# MPPT.net
KiCad netlist of a schematic drawn in Altium Designer
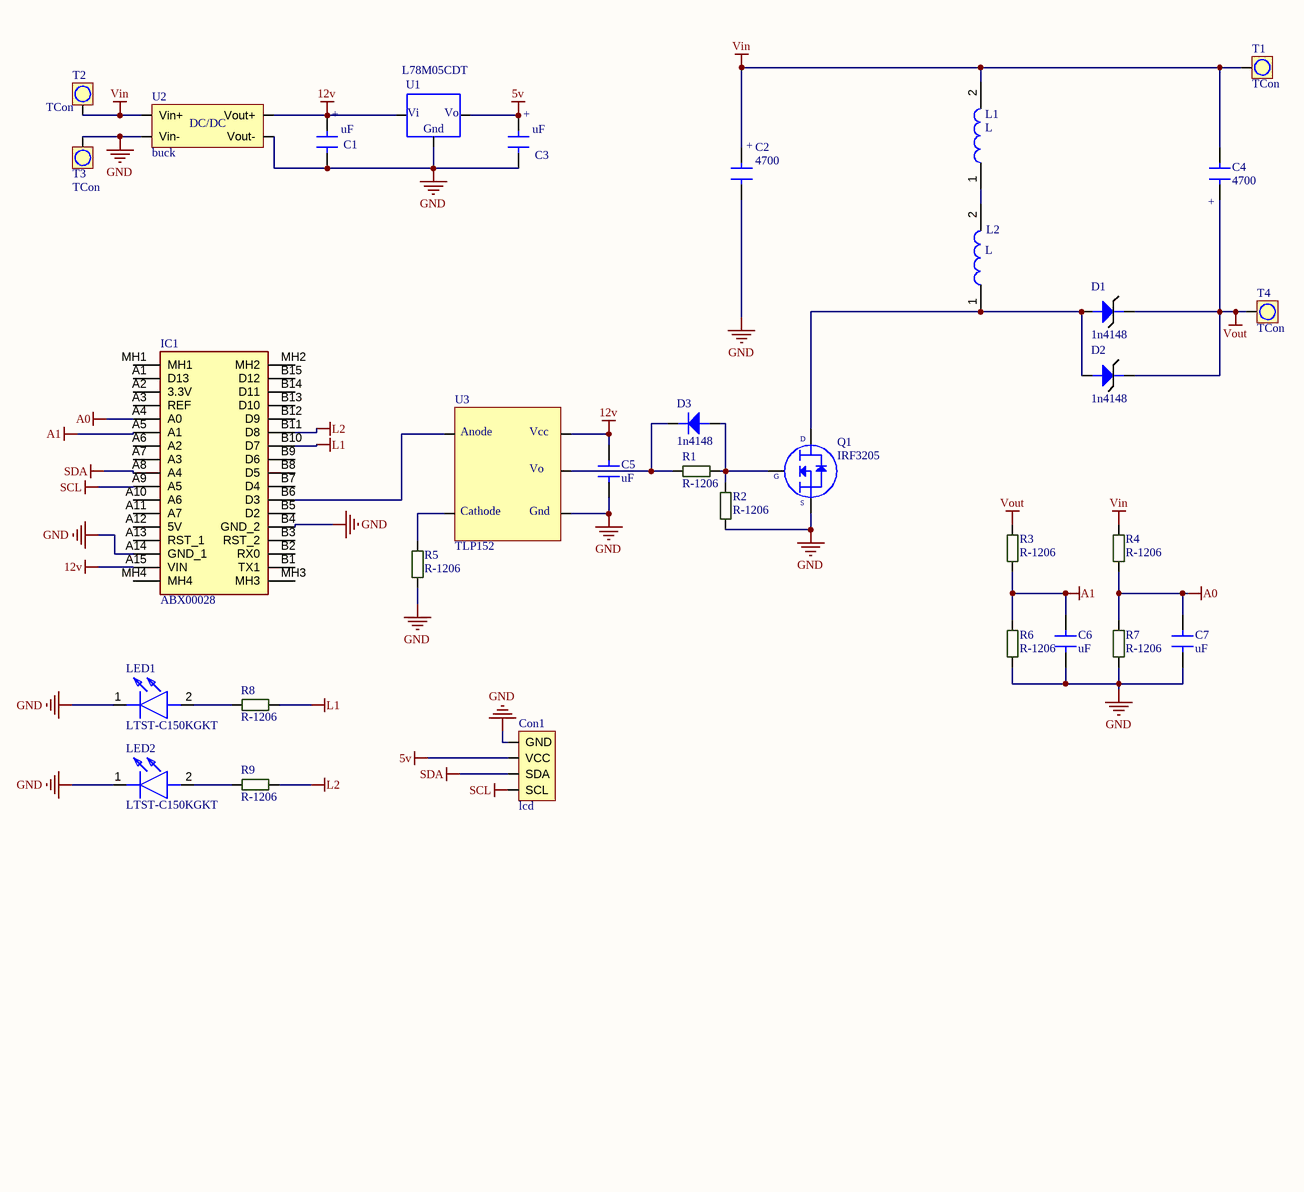
[diagram p0: MPPT.SchDoc]

(export (version "E")
  (design (tool "Eeschema 10.0.6"))
  (components
    (comp (ref "C1") (value "uF") (footprint "CapSmdElc") (libsource (lib "MPPT") (part "C-10uf")))
    (comp (ref "C2") (value "4700") (footprint "Koshin 63v 4700 cap") (libsource (lib "MPPT") (part "4700")))
    (comp (ref "C3") (value "uF") (footprint "CapSmdElc") (libsource (lib "MPPT") (part "C-10uf")))
    (comp (ref "C4") (value "4700") (footprint "Koshin 63v 4700 cap") (libsource (lib "MPPT") (part "4700")))
    (comp (ref "C5") (value "uF") (footprint "C-1206W") (libsource (lib "MPPT") (part "C-1206")))
    (comp (ref "C6") (value "uF") (footprint "C-1206W") (libsource (lib "MPPT") (part "C-1206")))
    (comp (ref "C7") (value "uF") (footprint "C-1206W") (libsource (lib "MPPT") (part "C-1206")))
    (comp (ref "Con1") (value "lcd") (footprint "lcd") (libsource (lib "MPPT") (part "lcd")))
    (comp (ref "D1")
      (value "1n4148")
      (footprint "TO254P483X1016X1994-3P")
      (description "Diode Small Signal Switching 100V 0.15A 2-Pin SOD-123 T/R")
      (fields
        (field (name "MANUFACTURER") "Vishay")
        (field (name "MANUFACTURER PART NUMBER") "1N4148W-E3-18")
      )
      (libsource (lib "MPPT") (part "schotky"))
    )
    (comp (ref "D2")
      (value "1n4148")
      (footprint "TO254P483X1016X1994-3P")
      (description "Diode Small Signal Switching 100V 0.15A 2-Pin SOD-123 T/R")
      (fields
        (field (name "MANUFACTURER") "Vishay")
        (field (name "MANUFACTURER PART NUMBER") "1N4148W-E3-18")
      )
      (libsource (lib "MPPT") (part "schotky"))
    )
    (comp (ref "D3")
      (value "1n4148")
      (footprint "SOD123")
      (description "Diode Small Signal Switching 100V 0.15A 2-Pin SOD-123 T/R")
      (fields
        (field (name "MANUFACTURER") "Vishay")
        (field (name "MANUFACTURER PART NUMBER") "1N4148W-E3-18")
      )
      (libsource (lib "MPPT") (part "1N5819w"))
    )
    (comp (ref "IC1")
      (value "ABX00028")
      (footprint "ABX00028")
      (description "Integrated Circuit")
      (fields (field (name "MOUSER PART NUMBER") "782-ABX00028") (field (name "RS PART NUMBER") "1927586"))
      (libsource (lib "MPPT") (part "ABX00028"))
    )
    (comp (ref "L1")
      (value "L")
      (footprint "L")
      (description "Inductor")
      (fields
        (field (name "MANUFACTURER_PART_NUMBER") "ATFC-0201-10N-G-T")
        (field (name "MOUSER PART NUMBER") "815-ATFC-0201-10NG")
      )
      (libsource (lib "MPPT") (part "L"))
    )
    (comp (ref "L2")
      (value "L")
      (footprint "L")
      (description "Inductor")
      (fields
        (field (name "MANUFACTURER_PART_NUMBER") "ATFC-0201-10N-G-T")
        (field (name "MOUSER PART NUMBER") "815-ATFC-0201-10NG")
      )
      (libsource (lib "MPPT") (part "L"))
    )
    (comp (ref "LED1")
      (value "LTST-C150KGKT")
      (footprint "L-1206")
      (description "LED")
      (fields
        (field (name "MOUSER PART NUMBER") "859-LTST-C150KGKT")
        (field (name "RS PART NUMBER") "6920871")
      )
      (libsource (lib "MPPT") (part "LTST-C150KGKT"))
    )
    (comp (ref "LED2")
      (value "LTST-C150KGKT")
      (footprint "L-1206")
      (description "LED")
      (fields
        (field (name "MOUSER PART NUMBER") "859-LTST-C150KGKT")
        (field (name "RS PART NUMBER") "6920871")
      )
      (libsource (lib "MPPT") (part "LTST-C150KGKT"))
    )
    (comp (ref "Q1")
      (value "IRF3205")
      (footprint "DPAK_TO263")
      (description "MOSFET N-CH 55V 110A D2PAK")
      (fields
        (field (name "MANUFACTURER") "Infineon")
        (field (name "MANUFACTURER PART NUMBER") "IRF3205STRLPBF")
      )
      (libsource (lib "MPPT") (part "IRF3205STRLPBF"))
    )
    (comp (ref "R1")
      (value "R-1206")
      (footprint "R-1206W")
      (description "Res1206")
      (libsource (lib "MPPT") (part "R-1206"))
    )
    (comp (ref "R2")
      (value "R-1206")
      (footprint "R-1206W")
      (description "Res1206")
      (libsource (lib "MPPT") (part "R-1206"))
    )
    (comp (ref "R3")
      (value "R-1206")
      (footprint "R-1206W")
      (description "Res1206")
      (libsource (lib "MPPT") (part "R-1206"))
    )
    (comp (ref "R4")
      (value "R-1206")
      (footprint "R-1206W")
      (description "Res1206")
      (libsource (lib "MPPT") (part "R-1206"))
    )
    (comp (ref "R5")
      (value "R-1206")
      (footprint "R-1206W")
      (description "Res1206")
      (libsource (lib "MPPT") (part "R-1206"))
    )
    (comp (ref "R6")
      (value "R-1206")
      (footprint "R-1206W")
      (description "Res1206")
      (libsource (lib "MPPT") (part "R-1206"))
    )
    (comp (ref "R7")
      (value "R-1206")
      (footprint "R-1206W")
      (description "Res1206")
      (libsource (lib "MPPT") (part "R-1206"))
    )
    (comp (ref "R8")
      (value "R-1206")
      (footprint "R-1206W")
      (description "Res1206")
      (libsource (lib "MPPT") (part "R-1206"))
    )
    (comp (ref "R9")
      (value "R-1206")
      (footprint "R-1206W")
      (description "Res1206")
      (libsource (lib "MPPT") (part "R-1206"))
    )
    (comp (ref "T1")
      (value "TCon")
      (footprint "2pinCon")
      (libsource (lib "MPPT") (part "Terminal Connector"))
    )
    (comp (ref "T2") (value "TCon") (footprint "2pinCon") (libsource (lib "") (part "Terminal Connector_2")))
    (comp (ref "T3") (value "TCon") (footprint "2pinCon") (libsource (lib "") (part "Terminal Connector_1")))
    (comp (ref "T4")
      (value "TCon")
      (footprint "2pinCon")
      (libsource (lib "MPPT") (part "Terminal Connector"))
    )
    (comp (ref "U1")
      (value "L78M05CDT")
      (footprint "TO-252")
      (description "Linear Voltage Regulators 15V 0.5A Positive")
      (fields
        (field (name "MANUFACTURER") "STMicroelectronics")
        (field (name "MANUFACTURER PART NUMBER") "L78M15CDT")
      )
      (libsource (lib "MPPT") (part "L78M15CDT"))
    )
    (comp (ref "U2") (value "buck") (footprint "DC_BOOST") (libsource (lib "MPPT") (part "buck")))
    (comp (ref "U3")
      (value "TLP152")
      (footprint "TLP152")
      (description "OPTOISO 3.75KV GATE DRIVER 6SO-5")
      (fields
        (field (name "MANUFACTURER") "Toshiba")
        (field (name "MANUFACTURER PART NUMBER") "TLP152(TPL,E")
      )
      (libsource (lib "MPPT") (part "TLP152(TPL,E"))
    )
  )
  (nets
    (net (code "1") (name "5v") (class "Default")
      (node (ref "C3") (pin "1") (pinfunction "1_1") (pintype "passive"))
      (node (ref "Con1") (pin "2") (pinfunction "VCC_2") (pintype "passive"))
      (node (ref "U1") (pin "3") (pinfunction "3_3") (pintype "passive"))
    )
    (net (code "2") (name "12v") (class "Default")
      (node (ref "C1") (pin "1") (pinfunction "1_1") (pintype "passive"))
      (node (ref "C5") (pin "2") (pinfunction "2_2") (pintype "passive"))
      (node (ref "IC1") (pin "A15") (pinfunction "VIN_A15") (pintype "passive"))
      (node (ref "U1") (pin "1") (pinfunction "1_1") (pintype "passive"))
      (node (ref "U2") (pin "4") (pinfunction "Vout+_4") (pintype "passive"))
      (node (ref "U3") (pin "5") (pinfunction "5_5") (pintype "passive"))
    )
    (net (code "3") (name "A0") (class "Default")
      (node (ref "C7") (pin "2") (pinfunction "2_2") (pintype "passive"))
      (node (ref "IC1") (pin "A4") (pinfunction "A0_A4") (pintype "passive"))
      (node (ref "R4") (pin "1") (pinfunction "1_1") (pintype "passive"))
      (node (ref "R7") (pin "2") (pinfunction "2_2") (pintype "passive"))
    )
    (net (code "4") (name "A1") (class "Default")
      (node (ref "C6") (pin "2") (pinfunction "2_2") (pintype "passive"))
      (node (ref "IC1") (pin "A5") (pinfunction "A1_A5") (pintype "passive"))
      (node (ref "R3") (pin "2") (pinfunction "2_2") (pintype "passive"))
      (node (ref "R6") (pin "2") (pinfunction "2_2") (pintype "passive"))
    )
    (net (code "5") (name "GND") (class "Default")
      (node (ref "C1") (pin "2") (pinfunction "2_2") (pintype "passive"))
      (node (ref "C2") (pin "1") (pinfunction "1_1") (pintype "passive"))
      (node (ref "C3") (pin "2") (pinfunction "2_2") (pintype "passive"))
      (node (ref "C5") (pin "1") (pinfunction "1_1") (pintype "passive"))
      (node (ref "C6") (pin "1") (pinfunction "1_1") (pintype "passive"))
      (node (ref "C7") (pin "1") (pinfunction "1_1") (pintype "passive"))
      (node (ref "Con1") (pin "1") (pinfunction "GND_1") (pintype "passive"))
      (node (ref "IC1") (pin "A14") (pinfunction "GND_1_A14") (pintype "passive"))
      (node (ref "IC1") (pin "B4") (pinfunction "GND_2_B4") (pintype "passive"))
      (node (ref "LED1") (pin "1") (pinfunction "K_1") (pintype "passive"))
      (node (ref "LED2") (pin "1") (pinfunction "K_1") (pintype "passive"))
      (node (ref "Q1") (pin "2") (pinfunction "2_2") (pintype "passive"))
      (node (ref "R2") (pin "1") (pinfunction "1_1") (pintype "passive"))
      (node (ref "R5") (pin "1") (pinfunction "1_1") (pintype "passive"))
      (node (ref "R6") (pin "1") (pinfunction "1_1") (pintype "passive"))
      (node (ref "R7") (pin "1") (pinfunction "1_1") (pintype "passive"))
      (node (ref "T3") (pin "1") (pinfunction "1_1") (pintype "passive"))
      (node (ref "U1") (pin "4") (pinfunction "4_4") (pintype "passive"))
      (node (ref "U2") (pin "2") (pinfunction "Vin-_2") (pintype "passive"))
      (node (ref "U2") (pin "3") (pinfunction "Vout-_3") (pintype "passive"))
      (node (ref "U3") (pin "3") (pinfunction "3_3") (pintype "passive"))
    )
    (net (code "6") (name "L1") (class "Default")
      (node (ref "IC1") (pin "B10") (pinfunction "D7_B10") (pintype "passive"))
      (node (ref "R8") (pin "2") (pinfunction "2_2") (pintype "passive"))
    )
    (net (code "7") (name "L2") (class "Default")
      (node (ref "IC1") (pin "B11") (pinfunction "D8_B11") (pintype "passive"))
      (node (ref "R9") (pin "2") (pinfunction "2_2") (pintype "passive"))
    )
    (net (code "8") (name "Net-(D1-Pad2)") (class "Default")
      (node (ref "D1") (pin "2") (pinfunction "2_2") (pintype "passive"))
      (node (ref "D2") (pin "2") (pinfunction "2_2") (pintype "passive"))
      (node (ref "L2") (pin "1") (pinfunction "1_1") (pintype "passive"))
      (node (ref "Q1") (pin "3") (pinfunction "3_3") (pintype "passive"))
    )
    (net (code "9") (name "Net-(D3-Pada)") (class "Default")
      (node (ref "D3") (pin "a") (pinfunction "a_a") (pintype "passive"))
      (node (ref "Q1") (pin "1") (pinfunction "1_1") (pintype "passive"))
      (node (ref "R1") (pin "2") (pinfunction "2_2") (pintype "passive"))
      (node (ref "R2") (pin "2") (pinfunction "2_2") (pintype "passive"))
    )
    (net (code "10") (name "Net-(D3-Padk)") (class "Default")
      (node (ref "D3") (pin "k") (pinfunction "k_k") (pintype "passive"))
      (node (ref "R1") (pin "1") (pinfunction "1_1") (pintype "passive"))
      (node (ref "U3") (pin "4") (pinfunction "4_4") (pintype "passive"))
    )
    (net (code "11") (name "Net-(IC1-D3)") (class "Default")
      (node (ref "IC1") (pin "B6") (pinfunction "D3_B6") (pintype "passive"))
      (node (ref "U3") (pin "1") (pinfunction "1_1") (pintype "passive"))
    )
    (net (code "12") (name "Net-(L1-Pad1)") (class "Default")
      (node (ref "L1") (pin "1") (pinfunction "1_1") (pintype "passive"))
      (node (ref "L2") (pin "2") (pinfunction "2_2") (pintype "passive"))
    )
    (net (code "13") (name "Net-(LED1-A)") (class "Default")
      (node (ref "LED1") (pin "2") (pinfunction "A_2") (pintype "passive"))
      (node (ref "R8") (pin "1") (pinfunction "1_1") (pintype "passive"))
    )
    (net (code "14") (name "Net-(LED2-A)") (class "Default")
      (node (ref "LED2") (pin "2") (pinfunction "A_2") (pintype "passive"))
      (node (ref "R9") (pin "1") (pinfunction "1_1") (pintype "passive"))
    )
    (net (code "15") (name "Net-(R5-Pad2)") (class "Default")
      (node (ref "R5") (pin "2") (pinfunction "2_2") (pintype "passive"))
      (node (ref "U3") (pin "2") (pinfunction "2_2") (pintype "passive"))
    )
    (net (code "16") (name "SCL") (class "Default")
      (node (ref "Con1") (pin "4") (pinfunction "SCL_4") (pintype "passive"))
      (node (ref "IC1") (pin "A9") (pinfunction "A5_A9") (pintype "passive"))
    )
    (net (code "17") (name "SDA") (class "Default")
      (node (ref "Con1") (pin "3") (pinfunction "SDA_3") (pintype "passive"))
      (node (ref "IC1") (pin "A8") (pinfunction "A4_A8") (pintype "passive"))
    )
    (net (code "18") (name "Vin") (class "Default")
      (node (ref "C2") (pin "2") (pinfunction "2_2") (pintype "passive"))
      (node (ref "C4") (pin "1") (pinfunction "1_1") (pintype "passive"))
      (node (ref "L1") (pin "2") (pinfunction "2_2") (pintype "passive"))
      (node (ref "R4") (pin "2") (pinfunction "2_2") (pintype "passive"))
      (node (ref "T1") (pin "1") (pinfunction "1_1") (pintype "passive"))
      (node (ref "T2") (pin "1") (pinfunction "1_1") (pintype "passive"))
      (node (ref "U2") (pin "1") (pinfunction "Vin+_1") (pintype "passive"))
    )
    (net (code "19") (name "Vout") (class "Default")
      (node (ref "C4") (pin "2") (pinfunction "2_2") (pintype "passive"))
      (node (ref "D1") (pin "1") (pinfunction "1_1") (pintype "passive"))
      (node (ref "D2") (pin "1") (pinfunction "1_1") (pintype "passive"))
      (node (ref "R3") (pin "1") (pinfunction "1_1") (pintype "passive"))
      (node (ref "T4") (pin "1") (pinfunction "1_1") (pintype "passive"))
    )
    (net (code "20") (name "unconnected-(IC1-3.3V-PadA2)") (class "Default")
      (node (ref "IC1") (pin "A2") (pinfunction "3.3V_A2") (pintype "passive"))
    )
    (net (code "21") (name "unconnected-(IC1-5V-PadA12)") (class "Default")
      (node (ref "IC1") (pin "A12") (pinfunction "5V_A12") (pintype "passive"))
    )
    (net (code "22") (name "unconnected-(IC1-A2-PadA6)") (class "Default")
      (node (ref "IC1") (pin "A6") (pinfunction "A2_A6") (pintype "passive"))
    )
    (net (code "23") (name "unconnected-(IC1-A3-PadA7)") (class "Default")
      (node (ref "IC1") (pin "A7") (pinfunction "A3_A7") (pintype "passive"))
    )
    (net (code "24") (name "unconnected-(IC1-A6-PadA10)") (class "Default")
      (node (ref "IC1") (pin "A10") (pinfunction "A6_A10") (pintype "passive"))
    )
    (net (code "25") (name "unconnected-(IC1-A7-PadA11)") (class "Default")
      (node (ref "IC1") (pin "A11") (pinfunction "A7_A11") (pintype "passive"))
    )
    (net (code "26") (name "unconnected-(IC1-D2-PadB5)") (class "Default")
      (node (ref "IC1") (pin "B5") (pinfunction "D2_B5") (pintype "passive"))
    )
    (net (code "27") (name "unconnected-(IC1-D4-PadB7)") (class "Default")
      (node (ref "IC1") (pin "B7") (pinfunction "D4_B7") (pintype "passive"))
    )
    (net (code "28") (name "unconnected-(IC1-D5-PadB8)") (class "Default")
      (node (ref "IC1") (pin "B8") (pinfunction "D5_B8") (pintype "passive"))
    )
    (net (code "29") (name "unconnected-(IC1-D6-PadB9)") (class "Default")
      (node (ref "IC1") (pin "B9") (pinfunction "D6_B9") (pintype "passive"))
    )
    (net (code "30") (name "unconnected-(IC1-D9-PadB12)") (class "Default")
      (node (ref "IC1") (pin "B12") (pinfunction "D9_B12") (pintype "passive"))
    )
    (net (code "31") (name "unconnected-(IC1-D10-PadB13)") (class "Default")
      (node (ref "IC1") (pin "B13") (pinfunction "D10_B13") (pintype "passive"))
    )
    (net (code "32") (name "unconnected-(IC1-D11-PadB14)") (class "Default")
      (node (ref "IC1") (pin "B14") (pinfunction "D11_B14") (pintype "passive"))
    )
    (net (code "33") (name "unconnected-(IC1-D12-PadB15)") (class "Default")
      (node (ref "IC1") (pin "B15") (pinfunction "D12_B15") (pintype "passive"))
    )
    (net (code "34") (name "unconnected-(IC1-D13-PadA1)") (class "Default")
      (node (ref "IC1") (pin "A1") (pinfunction "D13_A1") (pintype "passive"))
    )
    (net (code "35") (name "unconnected-(IC1-PadMH1)") (class "Default")
      (node (ref "IC1") (pin "MH1") (pinfunction "MH1_MH1") (pintype "passive"))
    )
    (net (code "36") (name "unconnected-(IC1-PadMH2)") (class "Default")
      (node (ref "IC1") (pin "MH2") (pinfunction "MH2_MH2") (pintype "passive"))
    )
    (net (code "37") (name "unconnected-(IC1-PadMH3)") (class "Default")
      (node (ref "IC1") (pin "MH3") (pinfunction "MH3_MH3") (pintype "passive"))
    )
    (net (code "38") (name "unconnected-(IC1-PadMH4)") (class "Default")
      (node (ref "IC1") (pin "MH4") (pinfunction "MH4_MH4") (pintype "passive"))
    )
    (net (code "39") (name "unconnected-(IC1-REF-PadA3)") (class "Default")
      (node (ref "IC1") (pin "A3") (pinfunction "REF_A3") (pintype "passive"))
    )
    (net (code "40") (name "unconnected-(IC1-RST_1-PadA13)") (class "Default")
      (node (ref "IC1") (pin "A13") (pinfunction "RST_1_A13") (pintype "passive"))
    )
    (net (code "41") (name "unconnected-(IC1-RST_2-PadB3)") (class "Default")
      (node (ref "IC1") (pin "B3") (pinfunction "RST_2_B3") (pintype "passive"))
    )
    (net (code "42") (name "unconnected-(IC1-RX0-PadB2)") (class "Default")
      (node (ref "IC1") (pin "B2") (pinfunction "RX0_B2") (pintype "passive"))
    )
    (net (code "43") (name "unconnected-(IC1-TX1-PadB1)") (class "Default")
      (node (ref "IC1") (pin "B1") (pinfunction "TX1_B1") (pintype "passive"))
    )
  )
)
